# Main.net
KiCad netlist of a schematic drawn in EAGLE
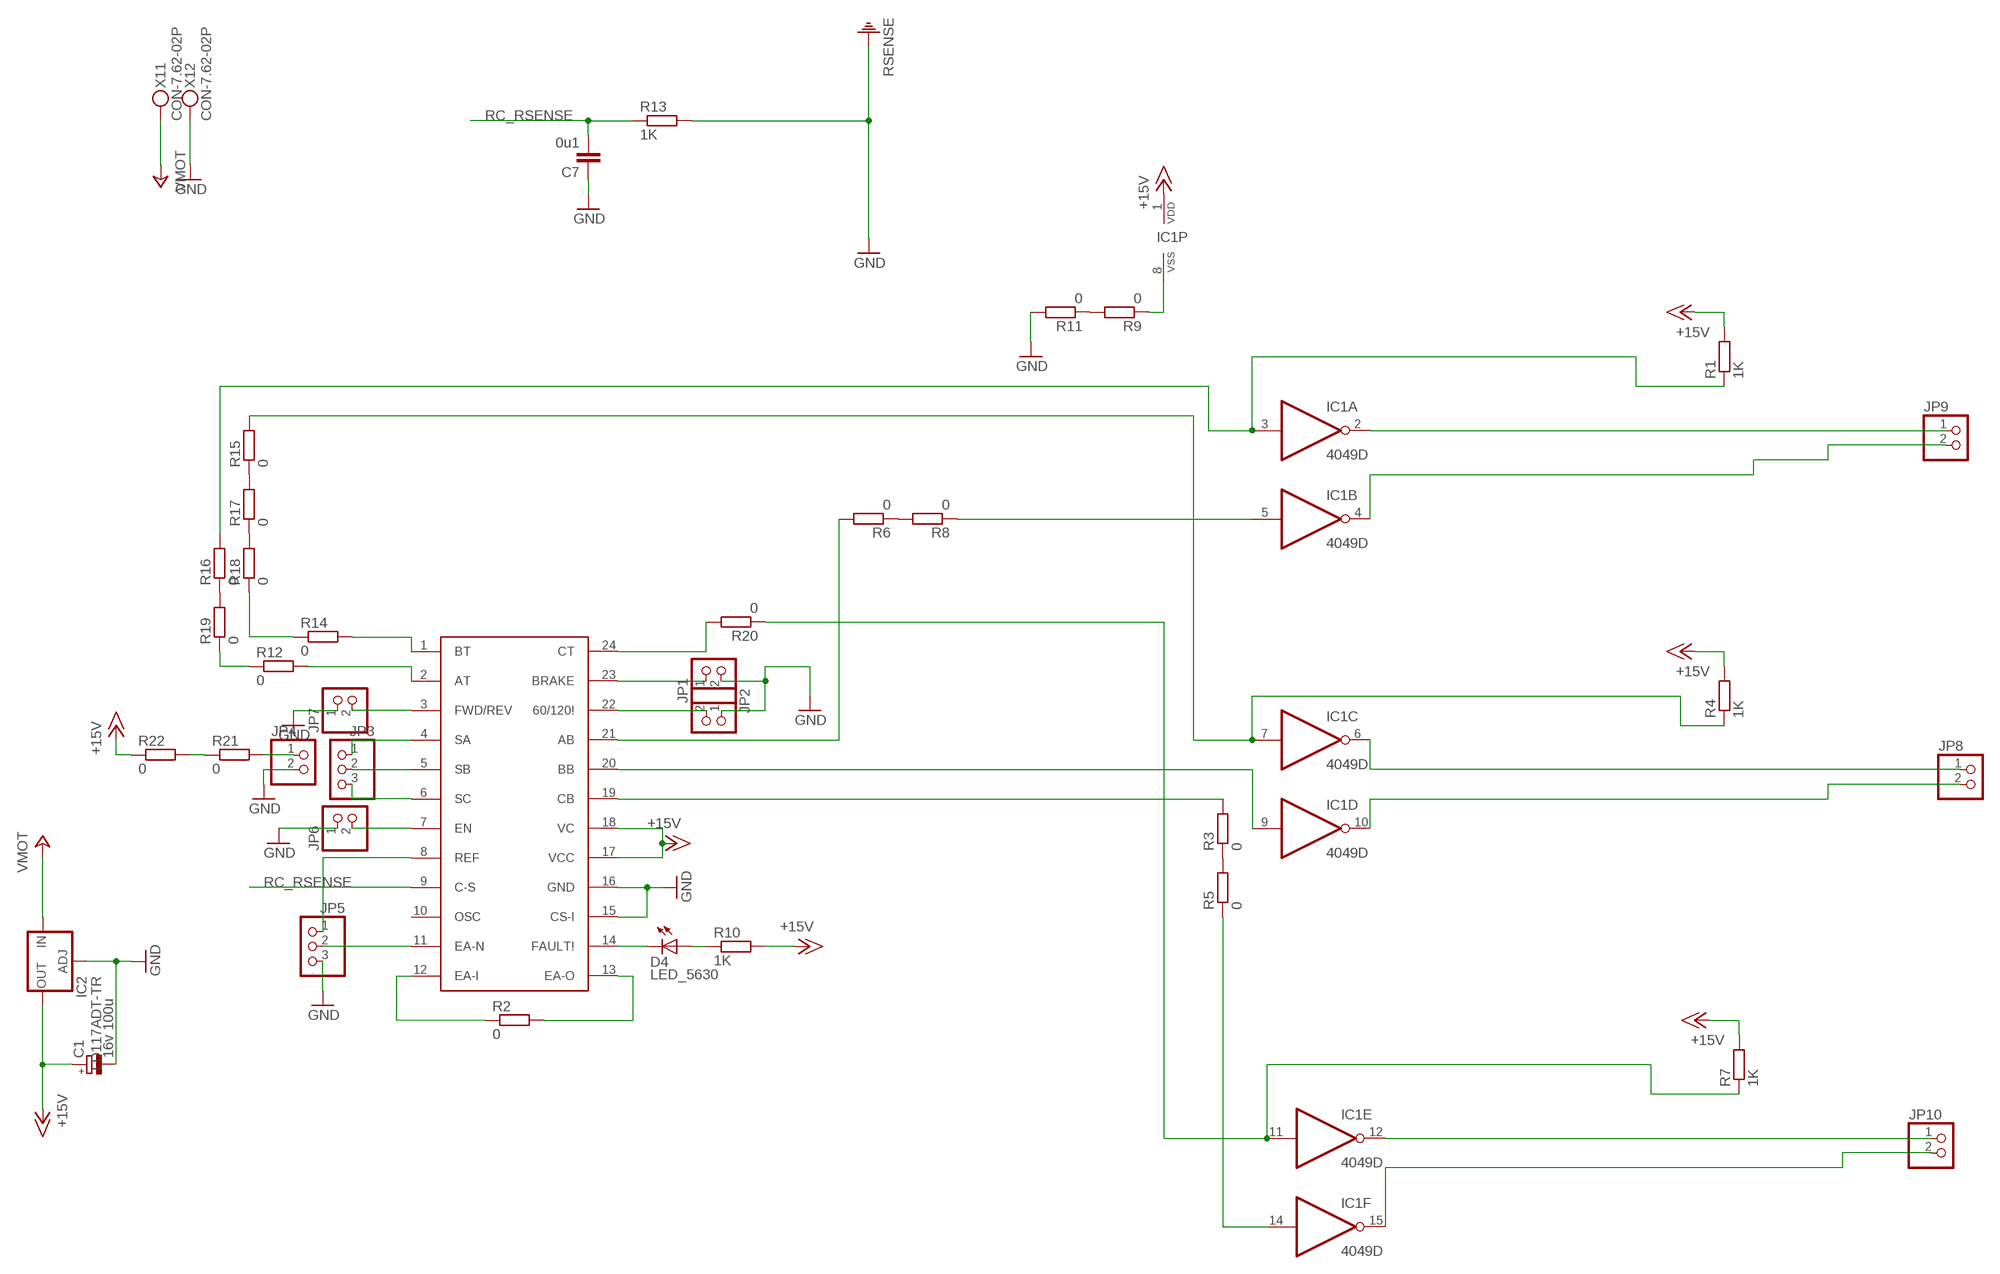
[diagram p0: schematic, sheet 1]

(export (version "E")
  (design (tool "Eeschema 10.0.6"))
  (components
    (comp (ref "C1")
      (value "16v 100u")
      (footprint "eagle-import:E2,5-7")
      (libsource (lib "eagle-import") (part "CPOL-EUE2.5-7"))
    )
    (comp (ref "C7")
      (value "0u1")
      (footprint "eagle-import:C0805")
      (libsource (lib "eagle-import") (part "CAP_0805"))
    )
    (comp (ref "D4")
      (value "LED_5630")
      (footprint "eagle-import:LED5730")
      (libsource (lib "eagle-import") (part "LED_5630"))
    )
    (comp (ref "IC1")
      (value "4049D")
      (footprint "eagle-import:SO16")
      (libsource (lib "eagle-import") (part "4049D"))
    )
    (comp (ref "IC2")
      (value "LD117ADT-TR")
      (footprint "eagle-import:DPACK")
      (libsource (lib "eagle-import") (part "LD117A?DT-TR"))
    )
    (comp (ref "JP1")
      (value "PINHD-1X2")
      (footprint "eagle-import:1X02")
      (libsource (lib "eagle-import") (part "PINHD-1X2"))
    )
    (comp (ref "JP2")
      (value "PINHD-1X2")
      (footprint "eagle-import:1X02")
      (libsource (lib "eagle-import") (part "PINHD-1X2"))
    )
    (comp (ref "JP3")
      (value "PINHD-1X3")
      (footprint "eagle-import:1X03")
      (libsource (lib "eagle-import") (part "PINHD-1X3"))
    )
    (comp (ref "JP4")
      (value "PINHD-1X2")
      (footprint "eagle-import:1X02")
      (libsource (lib "eagle-import") (part "PINHD-1X2"))
    )
    (comp (ref "JP5")
      (value "PINHD-1X3")
      (footprint "eagle-import:1X03")
      (libsource (lib "eagle-import") (part "PINHD-1X3"))
    )
    (comp (ref "JP6")
      (value "PINHD-1X2")
      (footprint "eagle-import:1X02")
      (libsource (lib "eagle-import") (part "PINHD-1X2"))
    )
    (comp (ref "JP7")
      (value "PINHD-1X2")
      (footprint "eagle-import:1X02")
      (libsource (lib "eagle-import") (part "PINHD-1X2"))
    )
    (comp (ref "JP8")
      (value "PINHD-1X2")
      (footprint "eagle-import:1X02")
      (libsource (lib "eagle-import") (part "PINHD-1X2"))
    )
    (comp (ref "JP9")
      (value "PINHD-1X2")
      (footprint "eagle-import:1X02")
      (libsource (lib "eagle-import") (part "PINHD-1X2"))
    )
    (comp (ref "JP10")
      (value "PINHD-1X2")
      (footprint "eagle-import:1X02")
      (libsource (lib "eagle-import") (part "PINHD-1X2"))
    )
    (comp (ref "R1")
      (value "1K")
      (footprint "eagle-import:R0805")
      (libsource (lib "eagle-import") (part "R_0805"))
    )
    (comp (ref "R2")
      (value "0")
      (footprint "eagle-import:R0805")
      (libsource (lib "eagle-import") (part "R_0805"))
    )
    (comp (ref "R3")
      (value "0")
      (footprint "eagle-import:R0805")
      (libsource (lib "eagle-import") (part "R_0805"))
    )
    (comp (ref "R4")
      (value "1K")
      (footprint "eagle-import:R0805")
      (libsource (lib "eagle-import") (part "R_0805"))
    )
    (comp (ref "R5")
      (value "0")
      (footprint "eagle-import:R0805")
      (libsource (lib "eagle-import") (part "R_0805"))
    )
    (comp (ref "R6")
      (value "0")
      (footprint "eagle-import:R0805")
      (libsource (lib "eagle-import") (part "R_0805"))
    )
    (comp (ref "R7")
      (value "1K")
      (footprint "eagle-import:R0805")
      (libsource (lib "eagle-import") (part "R_0805"))
    )
    (comp (ref "R8")
      (value "0")
      (footprint "eagle-import:R0805")
      (libsource (lib "eagle-import") (part "R_0805"))
    )
    (comp (ref "R9")
      (value "0")
      (footprint "eagle-import:R1206")
      (libsource (lib "eagle-import") (part "R_1206"))
    )
    (comp (ref "R10")
      (value "1K")
      (footprint "eagle-import:R0805")
      (libsource (lib "eagle-import") (part "R_0805"))
    )
    (comp (ref "R11")
      (value "0")
      (footprint "eagle-import:R0805")
      (libsource (lib "eagle-import") (part "R_0805"))
    )
    (comp (ref "R12")
      (value "0")
      (footprint "eagle-import:R0805")
      (libsource (lib "eagle-import") (part "R_0805"))
    )
    (comp (ref "R13")
      (value "1K")
      (footprint "eagle-import:R0805")
      (libsource (lib "eagle-import") (part "R_0805"))
    )
    (comp (ref "R14")
      (value "0")
      (footprint "eagle-import:R0805")
      (libsource (lib "eagle-import") (part "R_0805"))
    )
    (comp (ref "R15")
      (value "0")
      (footprint "eagle-import:R0805")
      (libsource (lib "eagle-import") (part "R_0805"))
    )
    (comp (ref "R16")
      (value "0")
      (footprint "eagle-import:R0805")
      (libsource (lib "eagle-import") (part "R_0805"))
    )
    (comp (ref "R17")
      (value "0")
      (footprint "eagle-import:R0805")
      (libsource (lib "eagle-import") (part "R_0805"))
    )
    (comp (ref "R18")
      (value "0")
      (footprint "eagle-import:R0805")
      (libsource (lib "eagle-import") (part "R_0805"))
    )
    (comp (ref "R19")
      (value "0")
      (footprint "eagle-import:R0805")
      (libsource (lib "eagle-import") (part "R_0805"))
    )
    (comp (ref "R20")
      (value "0")
      (footprint "eagle-import:R0805")
      (libsource (lib "eagle-import") (part "R_0805"))
    )
    (comp (ref "R21")
      (value "0")
      (footprint "eagle-import:R0805")
      (libsource (lib "eagle-import") (part "R_0805"))
    )
    (comp (ref "R22")
      (value "0")
      (footprint "eagle-import:R0805")
      (libsource (lib "eagle-import") (part "R_0805"))
    )
    (comp (ref "U$1")
      (value "IC-MC33035-D")
      (footprint "eagle-import:SO24W")
      (libsource (lib "eagle-import") (part "IC-MC33035-D"))
    )
    (comp (ref "X1")
      (value "CON-7.62-02P")
      (footprint "eagle-import:KF25C-7.62-02P-13")
      (libsource (lib "eagle-import") (part "CON-7.62-02P"))
    )
  )
  (nets
    (net (code "1") (name "+15V") (class "Default")
      (node (ref "C1") (pin "+") (pinfunction "+_+") (pintype "passive"))
      (node (ref "IC1") (pin "1") (pinfunction "VDD_1") (pintype "power_in"))
      (node (ref "IC2") (pin "4") (pinfunction "OUT_4") (pintype "passive"))
      (node (ref "R1") (pin "2") (pinfunction "2_2") (pintype "passive"))
      (node (ref "R10") (pin "2") (pinfunction "2_2") (pintype "passive"))
      (node (ref "R22") (pin "1") (pinfunction "1_1") (pintype "passive"))
      (node (ref "R4") (pin "2") (pinfunction "2_2") (pintype "passive"))
      (node (ref "R7") (pin "2") (pinfunction "2_2") (pintype "passive"))
      (node (ref "U$1") (pin "17") (pinfunction "VCC_17") (pintype "bidirectional"))
      (node (ref "U$1") (pin "18") (pinfunction "VC_18") (pintype "bidirectional"))
    )
    (net (code "2") (name "/RC_RSENSE") (class "Default")
      (node (ref "C7") (pin "2") (pinfunction "2_2") (pintype "passive"))
      (node (ref "R13") (pin "1") (pinfunction "1_1") (pintype "passive"))
      (node (ref "U$1") (pin "9") (pinfunction "C-S_9") (pintype "bidirectional"))
    )
    (net (code "3") (name "GND") (class "Default")
      (node (ref "C1") (pin "-") (pinfunction "-_-") (pintype "passive"))
      (node (ref "C7") (pin "1") (pinfunction "1_1") (pintype "passive"))
      (node (ref "IC2") (pin "1") (pinfunction "ADJ_1") (pintype "input"))
      (node (ref "JP1") (pin "2") (pinfunction "2_2") (pintype "passive"))
      (node (ref "JP2") (pin "1") (pinfunction "1_1") (pintype "passive"))
      (node (ref "JP4") (pin "2") (pinfunction "2_2") (pintype "passive"))
      (node (ref "JP5") (pin "3") (pinfunction "3_3") (pintype "passive"))
      (node (ref "JP6") (pin "1") (pinfunction "1_1") (pintype "passive"))
      (node (ref "JP7") (pin "1") (pinfunction "1_1") (pintype "passive"))
      (node (ref "R11") (pin "2") (pinfunction "2_2") (pintype "passive"))
      (node (ref "R13") (pin "2") (pinfunction "2_2") (pintype "passive"))
      (node (ref "U$1") (pin "15") (pinfunction "CS-I_15") (pintype "bidirectional"))
      (node (ref "U$1") (pin "16") (pinfunction "GND_16") (pintype "bidirectional"))
      (node (ref "X1") (pin "P$2") (pinfunction "KL_P$2") (pintype "passive"))
    )
    (net (code "4") (name "Net-(D4-A-PadA1)") (class "Default")
      (node (ref "D4") (pin "A") (pinfunction "A_A") (pintype "passive"))
      (node (ref "D4") (pin "A1") (pinfunction "A_A1") (pintype "passive"))
      (node (ref "R10") (pin "1") (pinfunction "1_1") (pintype "passive"))
    )
    (net (code "5") (name "Net-(IC1A-I)") (class "Default")
      (node (ref "IC1") (pin "3") (pinfunction "I_3") (pintype "input"))
      (node (ref "R1") (pin "1") (pinfunction "1_1") (pintype "passive"))
      (node (ref "R16") (pin "2") (pinfunction "2_2") (pintype "passive"))
    )
    (net (code "6") (name "Net-(IC1A-O)") (class "Default")
      (node (ref "IC1") (pin "2") (pinfunction "O_2") (pintype "output"))
      (node (ref "JP9") (pin "1") (pinfunction "1_1") (pintype "passive"))
    )
    (net (code "7") (name "Net-(IC1B-I)") (class "Default")
      (node (ref "IC1") (pin "5") (pinfunction "I_5") (pintype "input"))
      (node (ref "R8") (pin "1") (pinfunction "1_1") (pintype "passive"))
    )
    (net (code "8") (name "Net-(IC1B-O)") (class "Default")
      (node (ref "IC1") (pin "4") (pinfunction "O_4") (pintype "output"))
      (node (ref "JP9") (pin "2") (pinfunction "2_2") (pintype "passive"))
    )
    (net (code "9") (name "Net-(IC1C-I)") (class "Default")
      (node (ref "IC1") (pin "7") (pinfunction "I_7") (pintype "input"))
      (node (ref "R15") (pin "2") (pinfunction "2_2") (pintype "passive"))
      (node (ref "R4") (pin "1") (pinfunction "1_1") (pintype "passive"))
    )
    (net (code "10") (name "Net-(IC1C-O)") (class "Default")
      (node (ref "IC1") (pin "6") (pinfunction "O_6") (pintype "output"))
      (node (ref "JP8") (pin "1") (pinfunction "1_1") (pintype "passive"))
    )
    (net (code "11") (name "Net-(IC1D-I)") (class "Default")
      (node (ref "IC1") (pin "9") (pinfunction "I_9") (pintype "input"))
      (node (ref "U$1") (pin "20") (pinfunction "BB_20") (pintype "bidirectional"))
    )
    (net (code "12") (name "Net-(IC1D-O)") (class "Default")
      (node (ref "IC1") (pin "10") (pinfunction "O_10") (pintype "output"))
      (node (ref "JP8") (pin "2") (pinfunction "2_2") (pintype "passive"))
    )
    (net (code "13") (name "Net-(IC1E-I)") (class "Default")
      (node (ref "IC1") (pin "11") (pinfunction "I_11") (pintype "input"))
      (node (ref "R20") (pin "1") (pinfunction "1_1") (pintype "passive"))
      (node (ref "R7") (pin "1") (pinfunction "1_1") (pintype "passive"))
    )
    (net (code "14") (name "Net-(IC1E-O)") (class "Default")
      (node (ref "IC1") (pin "12") (pinfunction "O_12") (pintype "output"))
      (node (ref "JP10") (pin "1") (pinfunction "1_1") (pintype "passive"))
    )
    (net (code "15") (name "Net-(IC1F-I)") (class "Default")
      (node (ref "IC1") (pin "14") (pinfunction "I_14") (pintype "input"))
      (node (ref "R5") (pin "1") (pinfunction "1_1") (pintype "passive"))
    )
    (net (code "16") (name "Net-(IC1F-O)") (class "Default")
      (node (ref "IC1") (pin "15") (pinfunction "O_15") (pintype "output"))
      (node (ref "JP10") (pin "2") (pinfunction "2_2") (pintype "passive"))
    )
    (net (code "17") (name "Net-(IC1G-VSS)") (class "Default")
      (node (ref "IC1") (pin "8") (pinfunction "VSS_8") (pintype "power_in"))
      (node (ref "R9") (pin "1") (pinfunction "1_1") (pintype "passive"))
    )
    (net (code "18") (name "Net-(JP4-Pad1)") (class "Default")
      (node (ref "JP4") (pin "1") (pinfunction "1_1") (pintype "passive"))
      (node (ref "R21") (pin "2") (pinfunction "2_2") (pintype "passive"))
    )
    (net (code "19") (name "Net-(R3-Pad1)") (class "Default")
      (node (ref "R3") (pin "1") (pinfunction "1_1") (pintype "passive"))
      (node (ref "R5") (pin "2") (pinfunction "2_2") (pintype "passive"))
    )
    (net (code "20") (name "Net-(R6-Pad1)") (class "Default")
      (node (ref "R6") (pin "1") (pinfunction "1_1") (pintype "passive"))
      (node (ref "R8") (pin "2") (pinfunction "2_2") (pintype "passive"))
    )
    (net (code "21") (name "Net-(R11-Pad1)") (class "Default")
      (node (ref "R11") (pin "1") (pinfunction "1_1") (pintype "passive"))
      (node (ref "R9") (pin "2") (pinfunction "2_2") (pintype "passive"))
    )
    (net (code "22") (name "Net-(R12-Pad1)") (class "Default")
      (node (ref "R12") (pin "1") (pinfunction "1_1") (pintype "passive"))
      (node (ref "R19") (pin "1") (pinfunction "1_1") (pintype "passive"))
    )
    (net (code "23") (name "Net-(R14-Pad1)") (class "Default")
      (node (ref "R14") (pin "1") (pinfunction "1_1") (pintype "passive"))
      (node (ref "R18") (pin "1") (pinfunction "1_1") (pintype "passive"))
    )
    (net (code "24") (name "Net-(R15-Pad1)") (class "Default")
      (node (ref "R15") (pin "1") (pinfunction "1_1") (pintype "passive"))
      (node (ref "R17") (pin "2") (pinfunction "2_2") (pintype "passive"))
    )
    (net (code "25") (name "Net-(R16-Pad1)") (class "Default")
      (node (ref "R16") (pin "1") (pinfunction "1_1") (pintype "passive"))
      (node (ref "R19") (pin "2") (pinfunction "2_2") (pintype "passive"))
    )
    (net (code "26") (name "Net-(R17-Pad1)") (class "Default")
      (node (ref "R17") (pin "1") (pinfunction "1_1") (pintype "passive"))
      (node (ref "R18") (pin "2") (pinfunction "2_2") (pintype "passive"))
    )
    (net (code "27") (name "Net-(R21-Pad1)") (class "Default")
      (node (ref "R21") (pin "1") (pinfunction "1_1") (pintype "passive"))
      (node (ref "R22") (pin "2") (pinfunction "2_2") (pintype "passive"))
    )
    (net (code "28") (name "Net-(U$1-60{slash}120~{})") (class "Default")
      (node (ref "JP2") (pin "2") (pinfunction "2_2") (pintype "passive"))
      (node (ref "U$1") (pin "22") (pinfunction "60/120~{}_22") (pintype "bidirectional"))
    )
    (net (code "29") (name "Net-(U$1-AB)") (class "Default")
      (node (ref "R6") (pin "2") (pinfunction "2_2") (pintype "passive"))
      (node (ref "U$1") (pin "21") (pinfunction "AB_21") (pintype "bidirectional"))
    )
    (net (code "30") (name "Net-(U$1-AT)") (class "Default")
      (node (ref "R12") (pin "2") (pinfunction "2_2") (pintype "passive"))
      (node (ref "U$1") (pin "2") (pinfunction "AT_2") (pintype "bidirectional"))
    )
    (net (code "31") (name "Net-(U$1-BRAKE)") (class "Default")
      (node (ref "JP1") (pin "1") (pinfunction "1_1") (pintype "passive"))
      (node (ref "U$1") (pin "23") (pinfunction "BRAKE_23") (pintype "bidirectional"))
    )
    (net (code "32") (name "Net-(U$1-BT)") (class "Default")
      (node (ref "R14") (pin "2") (pinfunction "2_2") (pintype "passive"))
      (node (ref "U$1") (pin "1") (pinfunction "BT_1") (pintype "bidirectional"))
    )
    (net (code "33") (name "Net-(U$1-CB)") (class "Default")
      (node (ref "R3") (pin "2") (pinfunction "2_2") (pintype "passive"))
      (node (ref "U$1") (pin "19") (pinfunction "CB_19") (pintype "bidirectional"))
    )
    (net (code "34") (name "Net-(U$1-CT)") (class "Default")
      (node (ref "R20") (pin "2") (pinfunction "2_2") (pintype "passive"))
      (node (ref "U$1") (pin "24") (pinfunction "CT_24") (pintype "bidirectional"))
    )
    (net (code "35") (name "Net-(U$1-EA-I)") (class "Default")
      (node (ref "R2") (pin "1") (pinfunction "1_1") (pintype "passive"))
      (node (ref "U$1") (pin "12") (pinfunction "EA-I_12") (pintype "bidirectional"))
    )
    (net (code "36") (name "Net-(U$1-EA-N)") (class "Default")
      (node (ref "JP5") (pin "2") (pinfunction "2_2") (pintype "passive"))
      (node (ref "U$1") (pin "11") (pinfunction "EA-N_11") (pintype "bidirectional"))
    )
    (net (code "37") (name "Net-(U$1-EA-O)") (class "Default")
      (node (ref "R2") (pin "2") (pinfunction "2_2") (pintype "passive"))
      (node (ref "U$1") (pin "13") (pinfunction "EA-O_13") (pintype "bidirectional"))
    )
    (net (code "38") (name "Net-(U$1-EN)") (class "Default")
      (node (ref "JP6") (pin "2") (pinfunction "2_2") (pintype "passive"))
      (node (ref "U$1") (pin "7") (pinfunction "EN_7") (pintype "bidirectional"))
    )
    (net (code "39") (name "Net-(U$1-FAULT~{})") (class "Default")
      (node (ref "D4") (pin "C") (pinfunction "C_C") (pintype "passive"))
      (node (ref "U$1") (pin "14") (pinfunction "FAULT~{}_14") (pintype "bidirectional"))
    )
    (net (code "40") (name "Net-(U$1-FWD{slash}REV)") (class "Default")
      (node (ref "JP7") (pin "2") (pinfunction "2_2") (pintype "passive"))
      (node (ref "U$1") (pin "3") (pinfunction "FWD/REV_3") (pintype "bidirectional"))
    )
    (net (code "41") (name "Net-(U$1-REF)") (class "Default")
      (node (ref "JP5") (pin "1") (pinfunction "1_1") (pintype "passive"))
      (node (ref "U$1") (pin "8") (pinfunction "REF_8") (pintype "bidirectional"))
    )
    (net (code "42") (name "Net-(U$1-SA)") (class "Default")
      (node (ref "JP3") (pin "1") (pinfunction "1_1") (pintype "passive"))
      (node (ref "U$1") (pin "4") (pinfunction "SA_4") (pintype "bidirectional"))
    )
    (net (code "43") (name "Net-(U$1-SB)") (class "Default")
      (node (ref "JP3") (pin "2") (pinfunction "2_2") (pintype "passive"))
      (node (ref "U$1") (pin "5") (pinfunction "SB_5") (pintype "bidirectional"))
    )
    (net (code "44") (name "Net-(U$1-SC)") (class "Default")
      (node (ref "JP3") (pin "3") (pinfunction "3_3") (pintype "passive"))
      (node (ref "U$1") (pin "6") (pinfunction "SC_6") (pintype "bidirectional"))
    )
    (net (code "45") (name "VMOT") (class "Default")
      (node (ref "IC2") (pin "3") (pinfunction "IN_3") (pintype "input"))
      (node (ref "X1") (pin "P$1") (pinfunction "KL_P$1") (pintype "passive"))
    )
    (net (code "46") (name "unconnected-(U$1-OSC-Pad10)") (class "Default")
      (node (ref "U$1") (pin "10") (pinfunction "OSC_10") (pintype "bidirectional"))
    )
  )
)
